# 07-3V3_Monitor.net
KiCad netlist of a schematic drawn in Altium Designer
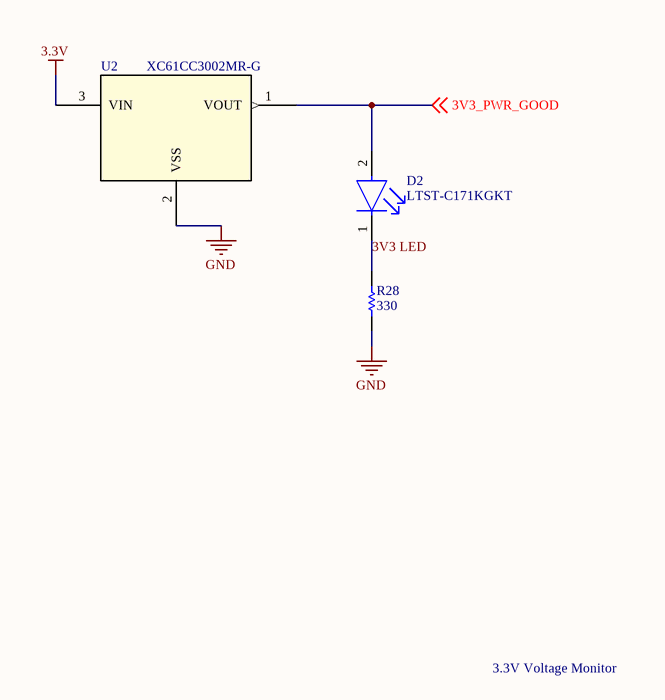
[diagram p0: 07-3V3_Monitor.SchDoc]

(export (version "E")
  (design (tool "Eeschema 10.0.6"))
  (components
    (comp (ref "D2")
      (value "LTST-C171KGKT")
      (footprint "FP-LTST-C171KGKT-MFG")
      (description "LED GREEN CLEAR SMD")
      (libsource (lib "Altium Content Vault") (part "8706943c75ba83719d021d2fdc84c58"))
    )
    (comp (ref "R28")
      (value "330")
      (footprint "RES_0805")
      (description "RES 330 OHM 1% 1/8W 0805")
      (fields (field (name "TOLERANCE") "1%"))
      (libsource (lib "team6") (part "RES_0805_R_330.00"))
    )
    (comp (ref "U2")
      (value "XC61CC3002MR-G")
      (footprint "XC61C_SOT-23_TOR")
      (description "IC SUPERVISOR 1 CHANNEL SOT23")
      (fields (field (name "COPYRIGHT") "Copyright (C) 2022 Ultra Librarian. All rights reserved."))
      (libsource (lib "team6") (part "XC61CC3002MR-G"))
    )
  )
  (nets
    (net (code "1") (name "/3V3 LED") (class "Default")
      (node (ref "D2") (pin "1") (pinfunction "C_1") (pintype "passive"))
      (node (ref "R28") (pin "2") (pinfunction "2_2") (pintype "passive"))
    )
    (net (code "2") (name "3.3V") (class "Default")
      (node (ref "U2") (pin "3") (pinfunction "VIN_3") (pintype "power_in"))
    )
    (net (code "3") (name "3V3_PWR_GOOD") (class "Default")
      (node (ref "D2") (pin "2") (pinfunction "A_2") (pintype "passive"))
      (node (ref "U2") (pin "1") (pinfunction "VOUT_1") (pintype "output"))
    )
    (net (code "4") (name "GND") (class "Default")
      (node (ref "R28") (pin "1") (pinfunction "1_1") (pintype "passive"))
      (node (ref "U2") (pin "2") (pinfunction "VSS_2") (pintype "passive"))
    )
  )
)
